# NES_IO_US.net
KiCad netlist of a schematic drawn in EAGLE
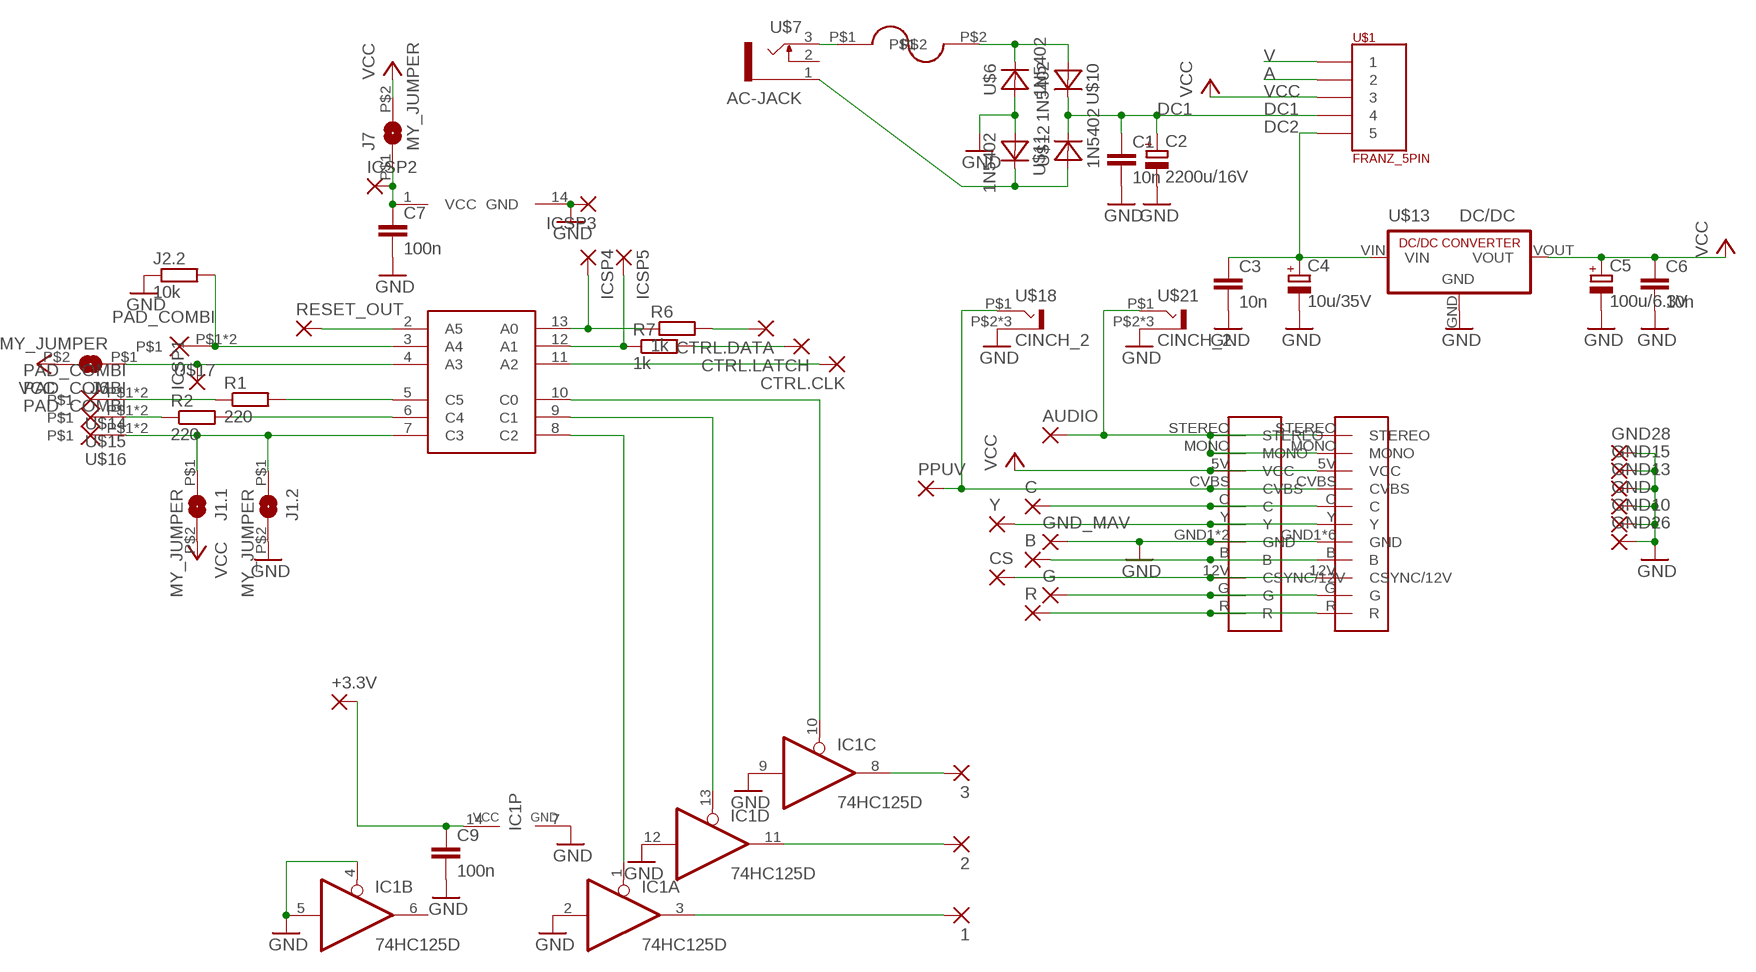
[diagram p0: schematic, sheet 1]

(export (version "E")
  (design (tool "Eeschema 10.0.6"))
  (components
    (comp (ref "+3.3V")
      (value "SMD2")
      (footprint "eagle-import:SMD1,27-2,54")
      (libsource (lib "eagle-import") (part "SMD2"))
    )
    (comp (ref "1")
      (value "SMD2")
      (footprint "eagle-import:SMD1,27-2,54")
      (libsource (lib "eagle-import") (part "SMD2"))
    )
    (comp (ref "2")
      (value "SMD2")
      (footprint "eagle-import:SMD1,27-2,54")
      (libsource (lib "eagle-import") (part "SMD2"))
    )
    (comp (ref "3")
      (value "SMD2")
      (footprint "eagle-import:SMD1,27-2,54")
      (libsource (lib "eagle-import") (part "SMD2"))
    )
    (comp (ref "AUDIO")
      (value "SMD2")
      (footprint "eagle-import:SMD1,27-2,54")
      (libsource (lib "eagle-import") (part "SMD2"))
    )
    (comp (ref "B")
      (value "SMD2")
      (footprint "eagle-import:SMD1,27-2,54")
      (libsource (lib "eagle-import") (part "SMD2"))
    )
    (comp (ref "C")
      (value "SMD2")
      (footprint "eagle-import:SMD1,27-2,54")
      (libsource (lib "eagle-import") (part "SMD2"))
    )
    (comp (ref "C1")
      (value "10n")
      (footprint "eagle-import:Z0805")
      (libsource (lib "eagle-import") (part "C0805"))
    )
    (comp (ref "C2")
      (value "2200u/16V")
      (footprint "eagle-import:E5-13")
      (libsource (lib "eagle-import") (part "resistor_CPOL-EUE5-13"))
    )
    (comp (ref "C3")
      (value "10n")
      (footprint "eagle-import:Z0805")
      (libsource (lib "eagle-import") (part "C0805"))
    )
    (comp (ref "C4")
      (value "10u/35V")
      (footprint "eagle-import:PANASONIC_B")
      (libsource (lib "eagle-import") (part "CPOL-EUB"))
    )
    (comp (ref "C5")
      (value "100u/6.3V")
      (footprint "eagle-import:PANASONIC_D")
      (libsource (lib "eagle-import") (part "CPOL-EUD"))
    )
    (comp (ref "C6")
      (value "10n")
      (footprint "eagle-import:Z0805")
      (libsource (lib "eagle-import") (part "C0805"))
    )
    (comp (ref "C7")
      (value "100n")
      (footprint "eagle-import:Z0805")
      (libsource (lib "eagle-import") (part "C0805"))
    )
    (comp (ref "C9")
      (value "100n")
      (footprint "eagle-import:Z0805")
      (libsource (lib "eagle-import") (part "C0805"))
    )
    (comp (ref "CS")
      (value "SMD2")
      (footprint "eagle-import:SMD1,27-2,54")
      (libsource (lib "eagle-import") (part "SMD2"))
    )
    (comp (ref "CTRL.CLK")
      (value "SMD2")
      (footprint "eagle-import:SMD1,27-2,54")
      (libsource (lib "eagle-import") (part "SMD2"))
    )
    (comp (ref "CTRL.DATA")
      (value "SMD2")
      (footprint "eagle-import:SMD1,27-2,54")
      (libsource (lib "eagle-import") (part "SMD2"))
    )
    (comp (ref "CTRL.LATCH")
      (value "SMD2")
      (footprint "eagle-import:SMD1,27-2,54")
      (libsource (lib "eagle-import") (part "SMD2"))
    )
    (comp (ref "G")
      (value "SMD2")
      (footprint "eagle-import:SMD1,27-2,54")
      (libsource (lib "eagle-import") (part "SMD2"))
    )
    (comp (ref "GND")
      (value "SMD5")
      (footprint "eagle-import:SMD2,54-5,08")
      (libsource (lib "eagle-import") (part "SMD5"))
    )
    (comp (ref "GND10")
      (value "SMD5")
      (footprint "eagle-import:SMD2,54-5,08")
      (libsource (lib "eagle-import") (part "SMD5"))
    )
    (comp (ref "GND13")
      (value "SMD5")
      (footprint "eagle-import:SMD2,54-5,08")
      (libsource (lib "eagle-import") (part "SMD5"))
    )
    (comp (ref "GND15")
      (value "SMD5")
      (footprint "eagle-import:SMD2,54-5,08")
      (libsource (lib "eagle-import") (part "SMD5"))
    )
    (comp (ref "GND26")
      (value "SMD5")
      (footprint "eagle-import:SMD2,54-5,08")
      (libsource (lib "eagle-import") (part "SMD5"))
    )
    (comp (ref "GND28")
      (value "SMD5")
      (footprint "eagle-import:SMD2,54-5,08")
      (libsource (lib "eagle-import") (part "SMD5"))
    )
    (comp (ref "GND_MAV")
      (value "SMD2")
      (footprint "eagle-import:SMD1,27-2,54")
      (libsource (lib "eagle-import") (part "SMD2"))
    )
    (comp (ref "IC1")
      (value "74HC125D")
      (footprint "eagle-import:SO14")
      (libsource (lib "eagle-import") (part "74125DHC"))
    )
    (comp (ref "ICSP1")
      (value "1,6/0,8")
      (footprint "eagle-import:1,6_0,8")
      (libsource (lib "eagle-import") (part "1,6/0,8"))
    )
    (comp (ref "ICSP2")
      (value "1,6/0,8")
      (footprint "eagle-import:1,6_0,8")
      (libsource (lib "eagle-import") (part "1,6/0,8"))
    )
    (comp (ref "ICSP3")
      (value "1,6/0,8")
      (footprint "eagle-import:1,6_0,8")
      (libsource (lib "eagle-import") (part "1,6/0,8"))
    )
    (comp (ref "ICSP4")
      (value "1,6/0,8")
      (footprint "eagle-import:1,6_0,8")
      (libsource (lib "eagle-import") (part "1,6/0,8"))
    )
    (comp (ref "ICSP5")
      (value "1,6/0,8")
      (footprint "eagle-import:1,6_0,8")
      (libsource (lib "eagle-import") (part "1,6/0,8"))
    )
    (comp (ref "J1.1")
      (value "MY_JUMPER")
      (footprint "eagle-import:MYJUMP")
      (libsource (lib "eagle-import") (part "MY_JUMPER"))
    )
    (comp (ref "J1.2")
      (value "MY_JUMPER")
      (footprint "eagle-import:MYJUMP")
      (libsource (lib "eagle-import") (part "MY_JUMPER"))
    )
    (comp (ref "J2.2")
      (value "10k")
      (footprint "eagle-import:Z0805")
      (libsource (lib "eagle-import") (part "R0805"))
    )
    (comp (ref "J6")
      (value "MY_JUMPER")
      (footprint "eagle-import:MYJUMP")
      (libsource (lib "eagle-import") (part "MY_JUMPER"))
    )
    (comp (ref "J7")
      (value "MY_JUMPER")
      (footprint "eagle-import:MYJUMP")
      (libsource (lib "eagle-import") (part "MY_JUMPER"))
    )
    (comp (ref "PPUV")
      (value "SMD2")
      (footprint "eagle-import:SMD1,27-2,54")
      (libsource (lib "eagle-import") (part "SMD2"))
    )
    (comp (ref "R")
      (value "SMD2")
      (footprint "eagle-import:SMD1,27-2,54")
      (libsource (lib "eagle-import") (part "SMD2"))
    )
    (comp (ref "R1")
      (value "220")
      (footprint "eagle-import:Z0805")
      (libsource (lib "eagle-import") (part "R0805"))
    )
    (comp (ref "R2")
      (value "220")
      (footprint "eagle-import:Z0805")
      (libsource (lib "eagle-import") (part "R0805"))
    )
    (comp (ref "R6")
      (value "1k")
      (footprint "eagle-import:Z0805")
      (libsource (lib "eagle-import") (part "R0805"))
    )
    (comp (ref "R7")
      (value "1k")
      (footprint "eagle-import:Z0805")
      (libsource (lib "eagle-import") (part "R0805"))
    )
    (comp (ref "RESET_OUT")
      (value "SMD2")
      (footprint "eagle-import:SMD1,27-2,54")
      (libsource (lib "eagle-import") (part "SMD2"))
    )
    (comp (ref "U$1")
      (value "FRANZ_5PIN")
      (footprint "eagle-import:5X2.22RM4")
      (libsource (lib "eagle-import") (part "FRANZ_5PIN"))
    )
    (comp (ref "U$2")
      (value "FUSEHOLDER")
      (footprint "eagle-import:FUSEHOLDER")
      (libsource (lib "eagle-import") (part "FUSEHOLDER"))
    )
    (comp (ref "U$5")
      (value "PIC16F630_SIMPLE")
      (footprint "eagle-import:PIC16F630")
      (libsource (lib "eagle-import") (part "PIC16F630_SIMPLE"))
    )
    (comp (ref "U$6")
      (value "1N5402")
      (footprint "eagle-import:DO201")
      (libsource (lib "eagle-import") (part "1N5402"))
    )
    (comp (ref "U$7")
      (value "AC-JACK")
      (footprint "eagle-import:AC-JACK")
      (libsource (lib "eagle-import") (part "AC-JACK"))
    )
    (comp (ref "U$10")
      (value "1N5402")
      (footprint "eagle-import:DO201")
      (libsource (lib "eagle-import") (part "1N5402"))
    )
    (comp (ref "U$11")
      (value "1N5402")
      (footprint "eagle-import:DO201")
      (libsource (lib "eagle-import") (part "1N5402"))
    )
    (comp (ref "U$12")
      (value "1N5402")
      (footprint "eagle-import:DO201")
      (libsource (lib "eagle-import") (part "1N5402"))
    )
    (comp (ref "U$13")
      (value "DC/DC")
      (footprint "eagle-import:RECOM")
      (libsource (lib "eagle-import") (part "DC/DC"))
    )
    (comp (ref "U$14")
      (value "PAD_COMBI")
      (footprint "eagle-import:PAD_COMBI")
      (libsource (lib "eagle-import") (part "PAD_COMBI"))
    )
    (comp (ref "U$15")
      (value "PAD_COMBI")
      (footprint "eagle-import:PAD_COMBI")
      (libsource (lib "eagle-import") (part "PAD_COMBI"))
    )
    (comp (ref "U$16")
      (value "PAD_COMBI")
      (footprint "eagle-import:PAD_COMBI")
      (libsource (lib "eagle-import") (part "PAD_COMBI"))
    )
    (comp (ref "U$17")
      (value "PAD_COMBI")
      (footprint "eagle-import:PAD_COMBI")
      (libsource (lib "eagle-import") (part "PAD_COMBI"))
    )
    (comp (ref "U$18")
      (value "CINCH_2")
      (footprint "eagle-import:CINCH_2")
      (libsource (lib "eagle-import") (part "CINCH_2"))
    )
    (comp (ref "U$19")
      (value "GC-MULTIAV")
      (footprint "eagle-import:GC-MULTIAV")
      (libsource (lib "eagle-import") (part "GC-MULTIAV"))
    )
    (comp (ref "U$20")
      (value "SNES-MULTIAV2")
      (footprint "eagle-import:SNES-MULTIAV2")
      (libsource (lib "eagle-import") (part "SNES-MULTIAV2"))
    )
    (comp (ref "U$21")
      (value "CINCH_2")
      (footprint "eagle-import:CINCH_2")
      (libsource (lib "eagle-import") (part "CINCH_2"))
    )
    (comp (ref "Y")
      (value "SMD2")
      (footprint "eagle-import:SMD1,27-2,54")
      (libsource (lib "eagle-import") (part "SMD2"))
    )
  )
  (nets
    (net (code "1") (name "/A") (class "Default")
      (node (ref "U$1") (pin "P$2") (pinfunction "2_P$2") (pintype "bidirectional"))
    )
    (net (code "2") (name "/DC1") (class "Default")
      (node (ref "C1") (pin "1") (pinfunction "1_1") (pintype "passive"))
      (node (ref "C2") (pin "+") (pinfunction "+_+") (pintype "passive"))
      (node (ref "U$1") (pin "P$4") (pinfunction "4_P$4") (pintype "bidirectional"))
      (node (ref "U$10") (pin "C") (pinfunction "C_C") (pintype "passive"))
      (node (ref "U$12") (pin "C") (pinfunction "C_C") (pintype "passive"))
    )
    (net (code "3") (name "/DC2") (class "Default")
      (node (ref "C3") (pin "1") (pinfunction "1_1") (pintype "passive"))
      (node (ref "C4") (pin "+") (pinfunction "+_+") (pintype "passive"))
      (node (ref "U$1") (pin "P$5") (pinfunction "5_P$5") (pintype "bidirectional"))
      (node (ref "U$13") (pin "VIN") (pinfunction "VIN_VIN") (pintype "passive"))
    )
    (net (code "4") (name "/V") (class "Default")
      (node (ref "U$1") (pin "P$1") (pinfunction "1_P$1") (pintype "bidirectional"))
    )
    (net (code "5") (name "GND") (class "Default")
      (node (ref "C1") (pin "2") (pinfunction "2_2") (pintype "passive"))
      (node (ref "C2") (pin "-") (pinfunction "-_-") (pintype "passive"))
      (node (ref "C3") (pin "2") (pinfunction "2_2") (pintype "passive"))
      (node (ref "C4") (pin "-") (pinfunction "-_-") (pintype "passive"))
      (node (ref "C5") (pin "-") (pinfunction "-_-") (pintype "passive"))
      (node (ref "C6") (pin "2") (pinfunction "2_2") (pintype "passive"))
      (node (ref "C7") (pin "2") (pinfunction "2_2") (pintype "passive"))
      (node (ref "C9") (pin "2") (pinfunction "2_2") (pintype "passive"))
      (node (ref "GND") (pin "1") (pinfunction "P_1") (pintype "passive"))
      (node (ref "GND10") (pin "1") (pinfunction "P_1") (pintype "passive"))
      (node (ref "GND13") (pin "1") (pinfunction "P_1") (pintype "passive"))
      (node (ref "GND15") (pin "1") (pinfunction "P_1") (pintype "passive"))
      (node (ref "GND26") (pin "1") (pinfunction "P_1") (pintype "passive"))
      (node (ref "GND28") (pin "1") (pinfunction "P_1") (pintype "passive"))
      (node (ref "GND_MAV") (pin "1") (pinfunction "P_1") (pintype "passive"))
      (node (ref "IC1") (pin "12") (pinfunction "I_12") (pintype "input"))
      (node (ref "IC1") (pin "2") (pinfunction "I_2") (pintype "input"))
      (node (ref "IC1") (pin "4") (pinfunction "OE_4") (pintype "input"))
      (node (ref "IC1") (pin "5") (pinfunction "I_5") (pintype "input"))
      (node (ref "IC1") (pin "7") (pinfunction "GND_7") (pintype "power_in"))
      (node (ref "IC1") (pin "9") (pinfunction "I_9") (pintype "input"))
      (node (ref "ICSP3") (pin "1") (pinfunction "P_1") (pintype "passive"))
      (node (ref "J1.2") (pin "P$2") (pinfunction "2_P$2") (pintype "passive"))
      (node (ref "J2.2") (pin "1") (pinfunction "1_1") (pintype "passive"))
      (node (ref "U$11") (pin "A") (pinfunction "A_A") (pintype "passive"))
      (node (ref "U$13") (pin "GND") (pinfunction "GND_GND") (pintype "passive"))
      (node (ref "U$18") (pin "P$2") (pinfunction "S_P$2") (pintype "passive"))
      (node (ref "U$18") (pin "P$3") (pinfunction "S_P$3") (pintype "passive"))
      (node (ref "U$18") (pin "P$4") (pinfunction "S_P$4") (pintype "passive"))
      (node (ref "U$19") (pin "GND1") (pinfunction "GND_GND1") (pintype "output"))
      (node (ref "U$19") (pin "GND2") (pinfunction "GND_GND2") (pintype "output"))
      (node (ref "U$19") (pin "GND3") (pinfunction "GND_GND3") (pintype "output"))
      (node (ref "U$19") (pin "GND4") (pinfunction "GND_GND4") (pintype "output"))
      (node (ref "U$19") (pin "GND5") (pinfunction "GND_GND5") (pintype "output"))
      (node (ref "U$19") (pin "GND6") (pinfunction "GND_GND6") (pintype "output"))
      (node (ref "U$20") (pin "GND1") (pinfunction "GND_GND1") (pintype "output"))
      (node (ref "U$20") (pin "GND2") (pinfunction "GND_GND2") (pintype "output"))
      (node (ref "U$21") (pin "P$2") (pinfunction "S_P$2") (pintype "passive"))
      (node (ref "U$21") (pin "P$3") (pinfunction "S_P$3") (pintype "passive"))
      (node (ref "U$21") (pin "P$4") (pinfunction "S_P$4") (pintype "passive"))
      (node (ref "U$5") (pin "14") (pinfunction "GND_14") (pintype "bidirectional"))
      (node (ref "U$6") (pin "A") (pinfunction "A_A") (pintype "passive"))
    )
    (net (code "6") (name "Net-(+3.3V-P)") (class "Default")
      (node (ref "+3.3V") (pin "1") (pinfunction "P_1") (pintype "passive"))
      (node (ref "C9") (pin "1") (pinfunction "1_1") (pintype "passive"))
      (node (ref "IC1") (pin "14") (pinfunction "VCC_14") (pintype "power_in"))
    )
    (net (code "7") (name "Net-(1-P)") (class "Default")
      (node (ref "1") (pin "1") (pinfunction "P_1") (pintype "passive"))
      (node (ref "IC1") (pin "3") (pinfunction "O_3") (pintype "tri_state"))
    )
    (net (code "8") (name "Net-(2-P)") (class "Default")
      (node (ref "2") (pin "1") (pinfunction "P_1") (pintype "passive"))
      (node (ref "IC1") (pin "11") (pinfunction "O_11") (pintype "tri_state"))
    )
    (net (code "9") (name "Net-(3-P)") (class "Default")
      (node (ref "3") (pin "1") (pinfunction "P_1") (pintype "passive"))
      (node (ref "IC1") (pin "8") (pinfunction "O_8") (pintype "tri_state"))
    )
    (net (code "10") (name "Net-(AUDIO-P)") (class "Default")
      (node (ref "AUDIO") (pin "1") (pinfunction "P_1") (pintype "passive"))
      (node (ref "U$19") (pin "MONO") (pinfunction "MONO_MONO") (pintype "output"))
      (node (ref "U$19") (pin "STEREO") (pinfunction "STEREO_STEREO") (pintype "output"))
      (node (ref "U$20") (pin "MONO") (pinfunction "MONO_MONO") (pintype "output"))
      (node (ref "U$20") (pin "STEREO") (pinfunction "STEREO_STEREO") (pintype "output"))
      (node (ref "U$21") (pin "P$1") (pinfunction "T_P$1") (pintype "passive"))
    )
    (net (code "11") (name "Net-(B-P)") (class "Default")
      (node (ref "B") (pin "1") (pinfunction "P_1") (pintype "passive"))
      (node (ref "U$19") (pin "B") (pinfunction "B_B") (pintype "output"))
      (node (ref "U$20") (pin "B") (pinfunction "B_B") (pintype "output"))
    )
    (net (code "12") (name "Net-(C-P)") (class "Default")
      (node (ref "C") (pin "1") (pinfunction "P_1") (pintype "passive"))
      (node (ref "U$19") (pin "C") (pinfunction "C_C") (pintype "output"))
      (node (ref "U$20") (pin "C") (pinfunction "C_C") (pintype "output"))
    )
    (net (code "13") (name "Net-(CS-P)") (class "Default")
      (node (ref "CS") (pin "1") (pinfunction "P_1") (pintype "passive"))
      (node (ref "U$19") (pin "12V") (pinfunction "CSYNC/12V_12V") (pintype "output"))
      (node (ref "U$20") (pin "12V") (pinfunction "CSYNC/12V_12V") (pintype "output"))
    )
    (net (code "14") (name "Net-(CTRL.CLK-P)") (class "Default")
      (node (ref "CTRL.CLK") (pin "1") (pinfunction "P_1") (pintype "passive"))
      (node (ref "U$5") (pin "11") (pinfunction "A2_11") (pintype "bidirectional"))
    )
    (net (code "15") (name "Net-(CTRL.DATA-P)") (class "Default")
      (node (ref "CTRL.DATA") (pin "1") (pinfunction "P_1") (pintype "passive"))
      (node (ref "R6") (pin "2") (pinfunction "2_2") (pintype "passive"))
    )
    (net (code "16") (name "Net-(CTRL.LATCH-P)") (class "Default")
      (node (ref "CTRL.LATCH") (pin "1") (pinfunction "P_1") (pintype "passive"))
      (node (ref "R7") (pin "2") (pinfunction "2_2") (pintype "passive"))
    )
    (net (code "17") (name "Net-(G-P)") (class "Default")
      (node (ref "G") (pin "1") (pinfunction "P_1") (pintype "passive"))
      (node (ref "U$19") (pin "G") (pinfunction "G_G") (pintype "output"))
      (node (ref "U$20") (pin "G") (pinfunction "G_G") (pintype "output"))
    )
    (net (code "18") (name "Net-(IC1A-OE)") (class "Default")
      (node (ref "IC1") (pin "1") (pinfunction "OE_1") (pintype "input"))
      (node (ref "U$5") (pin "8") (pinfunction "C2_8") (pintype "bidirectional"))
    )
    (net (code "19") (name "Net-(IC1C-OE)") (class "Default")
      (node (ref "IC1") (pin "10") (pinfunction "OE_10") (pintype "input"))
      (node (ref "U$5") (pin "10") (pinfunction "C0_10") (pintype "bidirectional"))
    )
    (net (code "20") (name "Net-(IC1D-OE)") (class "Default")
      (node (ref "IC1") (pin "13") (pinfunction "OE_13") (pintype "input"))
      (node (ref "U$5") (pin "9") (pinfunction "C1_9") (pintype "bidirectional"))
    )
    (net (code "21") (name "Net-(ICSP1-P)") (class "Default")
      (node (ref "ICSP1") (pin "1") (pinfunction "P_1") (pintype "passive"))
      (node (ref "J6") (pin "P$1") (pinfunction "1_P$1") (pintype "passive"))
      (node (ref "U$5") (pin "4") (pinfunction "A3_4") (pintype "bidirectional"))
    )
    (net (code "22") (name "Net-(ICSP2-P)") (class "Default")
      (node (ref "C7") (pin "1") (pinfunction "1_1") (pintype "passive"))
      (node (ref "ICSP2") (pin "1") (pinfunction "P_1") (pintype "passive"))
      (node (ref "J7") (pin "P$1") (pinfunction "1_P$1") (pintype "passive"))
      (node (ref "U$5") (pin "1") (pinfunction "VCC_1") (pintype "bidirectional"))
    )
    (net (code "23") (name "Net-(ICSP4-P)") (class "Default")
      (node (ref "ICSP4") (pin "1") (pinfunction "P_1") (pintype "passive"))
      (node (ref "R6") (pin "1") (pinfunction "1_1") (pintype "passive"))
      (node (ref "U$5") (pin "13") (pinfunction "A0_13") (pintype "bidirectional"))
    )
    (net (code "24") (name "Net-(ICSP5-P)") (class "Default")
      (node (ref "ICSP5") (pin "1") (pinfunction "P_1") (pintype "passive"))
      (node (ref "R7") (pin "1") (pinfunction "1_1") (pintype "passive"))
      (node (ref "U$5") (pin "12") (pinfunction "A1_12") (pintype "bidirectional"))
    )
    (net (code "25") (name "Net-(J1.1-1)") (class "Default")
      (node (ref "J1.1") (pin "P$1") (pinfunction "1_P$1") (pintype "passive"))
      (node (ref "J1.2") (pin "P$1") (pinfunction "1_P$1") (pintype "passive"))
      (node (ref "U$16") (pin "P$1") (pinfunction "P$1_P$1") (pintype "bidirectional"))
      (node (ref "U$16") (pin "P$2") (pinfunction "P$1_P$2") (pintype "bidirectional"))
      (node (ref "U$5") (pin "7") (pinfunction "C3_7") (pintype "bidirectional"))
    )
    (net (code "26") (name "Net-(PPUV-P)") (class "Default")
      (node (ref "PPUV") (pin "1") (pinfunction "P_1") (pintype "passive"))
      (node (ref "U$18") (pin "P$1") (pinfunction "T_P$1") (pintype "passive"))
      (node (ref "U$19") (pin "CVBS") (pinfunction "CVBS_CVBS") (pintype "output"))
      (node (ref "U$20") (pin "CVBS") (pinfunction "CVBS_CVBS") (pintype "output"))
    )
    (net (code "27") (name "Net-(R-P)") (class "Default")
      (node (ref "R") (pin "1") (pinfunction "P_1") (pintype "passive"))
      (node (ref "U$19") (pin "R") (pinfunction "R_R") (pintype "output"))
      (node (ref "U$20") (pin "R") (pinfunction "R_R") (pintype "output"))
    )
    (net (code "28") (name "Net-(R1-Pad1)") (class "Default")
      (node (ref "R1") (pin "1") (pinfunction "1_1") (pintype "passive"))
      (node (ref "U$14") (pin "P$1") (pinfunction "P$1_P$1") (pintype "bidirectional"))
      (node (ref "U$14") (pin "P$2") (pinfunction "P$1_P$2") (pintype "bidirectional"))
    )
    (net (code "29") (name "Net-(R2-Pad1)") (class "Default")
      (node (ref "R2") (pin "1") (pinfunction "1_1") (pintype "passive"))
      (node (ref "U$15") (pin "P$1") (pinfunction "P$1_P$1") (pintype "bidirectional"))
      (node (ref "U$15") (pin "P$2") (pinfunction "P$1_P$2") (pintype "bidirectional"))
    )
    (net (code "30") (name "Net-(RESET_OUT-P)") (class "Default")
      (node (ref "RESET_OUT") (pin "1") (pinfunction "P_1") (pintype "passive"))
      (node (ref "U$5") (pin "2") (pinfunction "A5_2") (pintype "bidirectional"))
    )
    (net (code "31") (name "Net-(U$2-PadP$1)") (class "Default")
      (node (ref "U$2") (pin "P$1") (pinfunction "P$1_P$1") (pintype "bidirectional"))
      (node (ref "U$7") (pin "3") (pinfunction "3_3") (pintype "passive"))
    )
    (net (code "32") (name "Net-(U$5A-A4)") (class "Default")
      (node (ref "J2.2") (pin "2") (pinfunction "2_2") (pintype "passive"))
      (node (ref "U$17") (pin "P$1") (pinfunction "P$1_P$1") (pintype "bidirectional"))
      (node (ref "U$17") (pin "P$2") (pinfunction "P$1_P$2") (pintype "bidirectional"))
      (node (ref "U$5") (pin "3") (pinfunction "A4_3") (pintype "bidirectional"))
    )
    (net (code "33") (name "Net-(U$5A-C4)") (class "Default")
      (node (ref "R2") (pin "2") (pinfunction "2_2") (pintype "passive"))
      (node (ref "U$5") (pin "6") (pinfunction "C4_6") (pintype "bidirectional"))
    )
    (net (code "34") (name "Net-(U$5A-C5)") (class "Default")
      (node (ref "R1") (pin "2") (pinfunction "2_2") (pintype "passive"))
      (node (ref "U$5") (pin "5") (pinfunction "C5_5") (pintype "bidirectional"))
    )
    (net (code "35") (name "Net-(U$7-5)") (class "Default")
      (node (ref "U$11") (pin "C") (pinfunction "C_C") (pintype "passive"))
      (node (ref "U$12") (pin "A") (pinfunction "A_A") (pintype "passive"))
      (node (ref "U$7") (pin "1") (pinfunction "5_1") (pintype "passive"))
    )
    (net (code "36") (name "Net-(U$10-PadA)") (class "Default")
      (node (ref "U$10") (pin "A") (pinfunction "A_A") (pintype "passive"))
      (node (ref "U$2") (pin "P$2") (pinfunction "P$2_P$2") (pintype "bidirectional"))
      (node (ref "U$6") (pin "C") (pinfunction "C_C") (pintype "passive"))
    )
    (net (code "37") (name "Net-(Y-P)") (class "Default")
      (node (ref "U$19") (pin "Y") (pinfunction "Y_Y") (pintype "output"))
      (node (ref "U$20") (pin "Y") (pinfunction "Y_Y") (pintype "output"))
      (node (ref "Y") (pin "1") (pinfunction "P_1") (pintype "passive"))
    )
    (net (code "38") (name "VCC") (class "Default")
      (node (ref "C5") (pin "+") (pinfunction "+_+") (pintype "passive"))
      (node (ref "C6") (pin "1") (pinfunction "1_1") (pintype "passive"))
      (node (ref "J1.1") (pin "P$2") (pinfunction "2_P$2") (pintype "passive"))
      (node (ref "J6") (pin "P$2") (pinfunction "2_P$2") (pintype "passive"))
      (node (ref "J7") (pin "P$2") (pinfunction "2_P$2") (pintype "passive"))
      (node (ref "U$1") (pin "P$3") (pinfunction "3_P$3") (pintype "bidirectional"))
      (node (ref "U$13") (pin "VOUT") (pinfunction "VOUT_VOUT") (pintype "passive"))
      (node (ref "U$19") (pin "5V") (pinfunction "VCC_5V") (pintype "output"))
      (node (ref "U$20") (pin "5V") (pinfunction "VCC_5V") (pintype "output"))
    )
    (net (code "39") (name "unconnected-(IC1B-O-Pad6)") (class "Default")
      (node (ref "IC1") (pin "6") (pinfunction "O_6") (pintype "tri_state"))
    )
    (net (code "40") (name "unconnected-(U$7-4-Pad2)") (class "Default")
      (node (ref "U$7") (pin "2") (pinfunction "4_2") (pintype "passive"))
    )
  )
)
